# tick-mk-4_7_1.net
KiCad netlist of a schematic drawn in EAGLE
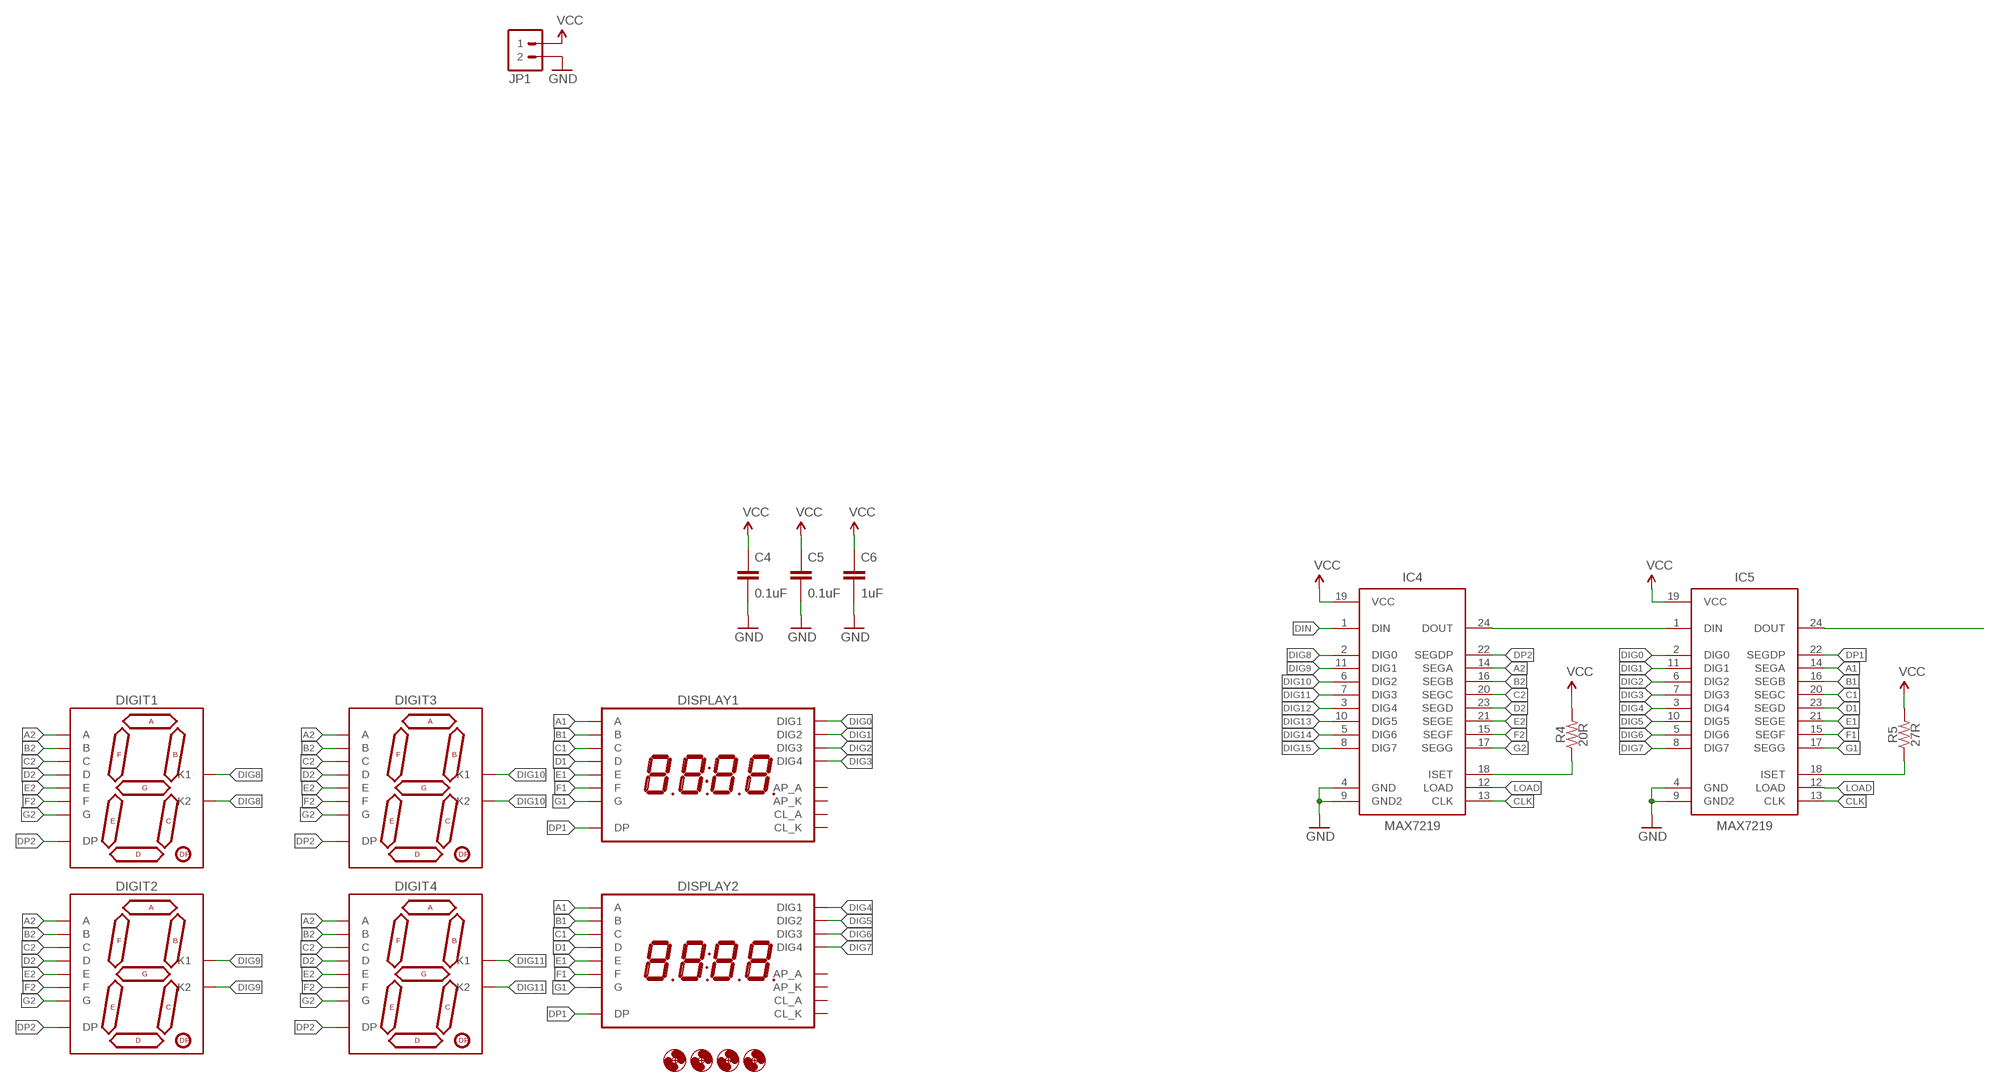
[diagram p0: schematic, sheet 1]

(export (version "E")
  (design (tool "Eeschema 10.0.6"))
  (components
    (comp (ref "C4")
      (value "0.1uF")
      (footprint "eagle-import:C025-024X044")
      (libsource (lib "eagle-import") (part "CAPACITOR-CERAMIC025-024X044"))
    )
    (comp (ref "C5")
      (value "0.1uF")
      (footprint "eagle-import:C025-024X044")
      (libsource (lib "eagle-import") (part "CAPACITOR-CERAMIC025-024X044"))
    )
    (comp (ref "C6")
      (value "1uF")
      (footprint "eagle-import:C025-024X044")
      (libsource (lib "eagle-import") (part "CAPACITOR-CERAMIC025-024X044"))
    )
    (comp (ref "DIGIT1")
      (value "7SEG_1DIGPTH-25.4MM-BARE")
      (footprint "eagle-import:7SEG_1DIG_25.4MM_NOSILK")
      (libsource (lib "eagle-import") (part "7SEG_1DIGPTH-25.4MM-BARE"))
    )
    (comp (ref "DIGIT2")
      (value "7SEG_1DIGPTH-25.4MM-BARE")
      (footprint "eagle-import:7SEG_1DIG_25.4MM_NOSILK")
      (libsource (lib "eagle-import") (part "7SEG_1DIGPTH-25.4MM-BARE"))
    )
    (comp (ref "DIGIT3")
      (value "7SEG_1DIGPTH-25.4MM-BARE")
      (footprint "eagle-import:7SEG_1DIG_25.4MM_NOSILK")
      (libsource (lib "eagle-import") (part "7SEG_1DIGPTH-25.4MM-BARE"))
    )
    (comp (ref "DIGIT4")
      (value "7SEG_1DIGPTH-25.4MM-BARE")
      (footprint "eagle-import:7SEG_1DIG_25.4MM_NOSILK")
      (libsource (lib "eagle-import") (part "7SEG_1DIGPTH-25.4MM-BARE"))
    )
    (comp (ref "DISPLAY1")
      (value "7SEG_4DIGIT_COLON_APOS")
      (footprint "eagle-import:7SEG_4DIG_10MM")
      (libsource (lib "eagle-import") (part "7SEG_4DIGIT_COLON_APOS"))
    )
    (comp (ref "DISPLAY2")
      (value "7SEG_4DIGIT_COLON_APOS")
      (footprint "eagle-import:7SEG_4DIG_10MM")
      (libsource (lib "eagle-import") (part "7SEG_4DIGIT_COLON_APOS"))
    )
    (comp (ref "H1")
      (value "HOLE#2")
      (footprint "eagle-import:HOLE-#2")
      (libsource (lib "eagle-import") (part "HOLE#2"))
    )
    (comp (ref "H2")
      (value "HOLE#2")
      (footprint "eagle-import:HOLE-#2")
      (libsource (lib "eagle-import") (part "HOLE#2"))
    )
    (comp (ref "H3")
      (value "HOLE#2")
      (footprint "eagle-import:HOLE-#2")
      (libsource (lib "eagle-import") (part "HOLE#2"))
    )
    (comp (ref "H4")
      (value "HOLE#2")
      (footprint "eagle-import:HOLE-#2")
      (libsource (lib "eagle-import") (part "HOLE#2"))
    )
    (comp (ref "IC4")
      (value "MAX7219")
      (footprint "eagle-import:SO24W")
      (libsource (lib "eagle-import") (part "MAX7219SOIC-W"))
    )
    (comp (ref "IC5")
      (value "MAX7219")
      (footprint "eagle-import:SO24W")
      (libsource (lib "eagle-import") (part "MAX7219SOIC-W"))
    )
    (comp (ref "JP1")
      (value "M02JST-XH-VERT")
      (footprint "eagle-import:JST-2-XH-VERT-PTH")
      (libsource (lib "eagle-import") (part "M02JST-XH-VERT"))
    )
    (comp (ref "R4")
      (value "20R")
      (footprint "eagle-import:RESISTOR-AXIAL-PTH-7.62MM")
      (libsource (lib "eagle-import") (part "RESISTORPTH-AXIAL-7.62MM"))
    )
    (comp (ref "R5")
      (value "27R")
      (footprint "eagle-import:RESISTOR-AXIAL-PTH-7.62MM")
      (libsource (lib "eagle-import") (part "RESISTORPTH-AXIAL-7.62MM"))
    )
  )
  (nets
    (net (code "1") (name "A1") (class "Default")
      (node (ref "DISPLAY1") (pin "14") (pinfunction "A_14") (pintype "passive"))
      (node (ref "DISPLAY2") (pin "14") (pinfunction "A_14") (pintype "passive"))
      (node (ref "IC5") (pin "14") (pinfunction "SEGA_14") (pintype "bidirectional"))
    )
    (net (code "2") (name "A2") (class "Default")
      (node (ref "DIGIT1") (pin "7") (pinfunction "A_7") (pintype "bidirectional"))
      (node (ref "DIGIT2") (pin "7") (pinfunction "A_7") (pintype "bidirectional"))
      (node (ref "DIGIT3") (pin "7") (pinfunction "A_7") (pintype "bidirectional"))
      (node (ref "DIGIT4") (pin "7") (pinfunction "A_7") (pintype "bidirectional"))
      (node (ref "IC4") (pin "14") (pinfunction "SEGA_14") (pintype "bidirectional"))
    )
    (net (code "3") (name "B1") (class "Default")
      (node (ref "DISPLAY1") (pin "16") (pinfunction "B_16") (pintype "passive"))
      (node (ref "DISPLAY2") (pin "16") (pinfunction "B_16") (pintype "passive"))
      (node (ref "IC5") (pin "16") (pinfunction "SEGB_16") (pintype "bidirectional"))
    )
    (net (code "4") (name "B2") (class "Default")
      (node (ref "DIGIT1") (pin "6") (pinfunction "B_6") (pintype "bidirectional"))
      (node (ref "DIGIT2") (pin "6") (pinfunction "B_6") (pintype "bidirectional"))
      (node (ref "DIGIT3") (pin "6") (pinfunction "B_6") (pintype "bidirectional"))
      (node (ref "DIGIT4") (pin "6") (pinfunction "B_6") (pintype "bidirectional"))
      (node (ref "IC4") (pin "16") (pinfunction "SEGB_16") (pintype "bidirectional"))
    )
    (net (code "5") (name "C1") (class "Default")
      (node (ref "DISPLAY1") (pin "13") (pinfunction "C_13") (pintype "passive"))
      (node (ref "DISPLAY2") (pin "13") (pinfunction "C_13") (pintype "passive"))
      (node (ref "IC5") (pin "20") (pinfunction "SEGC_20") (pintype "bidirectional"))
    )
    (net (code "6") (name "C2") (class "Default")
      (node (ref "DIGIT1") (pin "4") (pinfunction "C_4") (pintype "bidirectional"))
      (node (ref "DIGIT2") (pin "4") (pinfunction "C_4") (pintype "bidirectional"))
      (node (ref "DIGIT3") (pin "4") (pinfunction "C_4") (pintype "bidirectional"))
      (node (ref "DIGIT4") (pin "4") (pinfunction "C_4") (pintype "bidirectional"))
      (node (ref "IC4") (pin "20") (pinfunction "SEGC_20") (pintype "bidirectional"))
    )
    (net (code "7") (name "CLK") (class "Default")
      (node (ref "IC4") (pin "13") (pinfunction "CLK_13") (pintype "bidirectional"))
      (node (ref "IC5") (pin "13") (pinfunction "CLK_13") (pintype "bidirectional"))
    )
    (net (code "8") (name "D1") (class "Default")
      (node (ref "DISPLAY1") (pin "3") (pinfunction "D_3") (pintype "passive"))
      (node (ref "DISPLAY2") (pin "3") (pinfunction "D_3") (pintype "passive"))
      (node (ref "IC5") (pin "23") (pinfunction "SEGD_23") (pintype "bidirectional"))
    )
    (net (code "9") (name "D2") (class "Default")
      (node (ref "DIGIT1") (pin "2") (pinfunction "D_2") (pintype "bidirectional"))
      (node (ref "DIGIT2") (pin "2") (pinfunction "D_2") (pintype "bidirectional"))
      (node (ref "DIGIT3") (pin "2") (pinfunction "D_2") (pintype "bidirectional"))
      (node (ref "DIGIT4") (pin "2") (pinfunction "D_2") (pintype "bidirectional"))
      (node (ref "IC4") (pin "23") (pinfunction "SEGD_23") (pintype "bidirectional"))
    )
    (net (code "10") (name "DIG0") (class "Default")
      (node (ref "DISPLAY1") (pin "1") (pinfunction "DIG1_1") (pintype "passive"))
      (node (ref "IC5") (pin "2") (pinfunction "DIG0_2") (pintype "bidirectional"))
    )
    (net (code "11") (name "DIG1") (class "Default")
      (node (ref "DISPLAY1") (pin "2") (pinfunction "DIG2_2") (pintype "passive"))
      (node (ref "IC5") (pin "11") (pinfunction "DIG1_11") (pintype "bidirectional"))
    )
    (net (code "12") (name "DIG2") (class "Default")
      (node (ref "DISPLAY1") (pin "6") (pinfunction "DIG3_6") (pintype "passive"))
      (node (ref "IC5") (pin "6") (pinfunction "DIG2_6") (pintype "bidirectional"))
    )
    (net (code "13") (name "DIG3") (class "Default")
      (node (ref "DISPLAY1") (pin "8") (pinfunction "DIG4_8") (pintype "passive"))
      (node (ref "IC5") (pin "7") (pinfunction "DIG3_7") (pintype "bidirectional"))
    )
    (net (code "14") (name "DIG4") (class "Default")
      (node (ref "DISPLAY2") (pin "1") (pinfunction "DIG1_1") (pintype "passive"))
      (node (ref "IC5") (pin "3") (pinfunction "DIG4_3") (pintype "bidirectional"))
    )
    (net (code "15") (name "DIG5") (class "Default")
      (node (ref "DISPLAY2") (pin "2") (pinfunction "DIG2_2") (pintype "passive"))
      (node (ref "IC5") (pin "10") (pinfunction "DIG5_10") (pintype "bidirectional"))
    )
    (net (code "16") (name "DIG6") (class "Default")
      (node (ref "DISPLAY2") (pin "6") (pinfunction "DIG3_6") (pintype "passive"))
      (node (ref "IC5") (pin "5") (pinfunction "DIG6_5") (pintype "bidirectional"))
    )
    (net (code "17") (name "DIG7") (class "Default")
      (node (ref "DISPLAY2") (pin "8") (pinfunction "DIG4_8") (pintype "passive"))
      (node (ref "IC5") (pin "8") (pinfunction "DIG7_8") (pintype "bidirectional"))
    )
    (net (code "18") (name "DIG8") (class "Default")
      (node (ref "DIGIT1") (pin "3") (pinfunction "K1_3") (pintype "bidirectional"))
      (node (ref "DIGIT1") (pin "8") (pinfunction "K2_8") (pintype "bidirectional"))
      (node (ref "IC4") (pin "2") (pinfunction "DIG0_2") (pintype "bidirectional"))
    )
    (net (code "19") (name "DIG9") (class "Default")
      (node (ref "DIGIT2") (pin "3") (pinfunction "K1_3") (pintype "bidirectional"))
      (node (ref "DIGIT2") (pin "8") (pinfunction "K2_8") (pintype "bidirectional"))
      (node (ref "IC4") (pin "11") (pinfunction "DIG1_11") (pintype "bidirectional"))
    )
    (net (code "20") (name "DIG10") (class "Default")
      (node (ref "DIGIT3") (pin "3") (pinfunction "K1_3") (pintype "bidirectional"))
      (node (ref "DIGIT3") (pin "8") (pinfunction "K2_8") (pintype "bidirectional"))
      (node (ref "IC4") (pin "6") (pinfunction "DIG2_6") (pintype "bidirectional"))
    )
    (net (code "21") (name "DIG11") (class "Default")
      (node (ref "DIGIT4") (pin "3") (pinfunction "K1_3") (pintype "bidirectional"))
      (node (ref "DIGIT4") (pin "8") (pinfunction "K2_8") (pintype "bidirectional"))
      (node (ref "IC4") (pin "7") (pinfunction "DIG3_7") (pintype "bidirectional"))
    )
    (net (code "22") (name "DIG12") (class "Default")
      (node (ref "IC4") (pin "3") (pinfunction "DIG4_3") (pintype "bidirectional"))
    )
    (net (code "23") (name "DIG13") (class "Default")
      (node (ref "IC4") (pin "10") (pinfunction "DIG5_10") (pintype "bidirectional"))
    )
    (net (code "24") (name "DIG14") (class "Default")
      (node (ref "IC4") (pin "5") (pinfunction "DIG6_5") (pintype "bidirectional"))
    )
    (net (code "25") (name "DIG15") (class "Default")
      (node (ref "IC4") (pin "8") (pinfunction "DIG7_8") (pintype "bidirectional"))
    )
    (net (code "26") (name "DIN") (class "Default")
      (node (ref "IC4") (pin "1") (pinfunction "DIN_1") (pintype "bidirectional"))
    )
    (net (code "27") (name "DP1") (class "Default")
      (node (ref "DISPLAY1") (pin "7") (pinfunction "DP_7") (pintype "passive"))
      (node (ref "DISPLAY2") (pin "7") (pinfunction "DP_7") (pintype "passive"))
      (node (ref "IC5") (pin "22") (pinfunction "SEGDP_22") (pintype "bidirectional"))
    )
    (net (code "28") (name "DP2") (class "Default")
      (node (ref "DIGIT1") (pin "5") (pinfunction "DP_5") (pintype "bidirectional"))
      (node (ref "DIGIT2") (pin "5") (pinfunction "DP_5") (pintype "bidirectional"))
      (node (ref "DIGIT3") (pin "5") (pinfunction "DP_5") (pintype "bidirectional"))
      (node (ref "DIGIT4") (pin "5") (pinfunction "DP_5") (pintype "bidirectional"))
      (node (ref "IC4") (pin "22") (pinfunction "SEGDP_22") (pintype "bidirectional"))
    )
    (net (code "29") (name "E1") (class "Default")
      (node (ref "DISPLAY1") (pin "5") (pinfunction "E_5") (pintype "passive"))
      (node (ref "DISPLAY2") (pin "5") (pinfunction "E_5") (pintype "passive"))
      (node (ref "IC5") (pin "21") (pinfunction "SEGE_21") (pintype "bidirectional"))
    )
    (net (code "30") (name "E2") (class "Default")
      (node (ref "DIGIT1") (pin "1") (pinfunction "E_1") (pintype "bidirectional"))
      (node (ref "DIGIT2") (pin "1") (pinfunction "E_1") (pintype "bidirectional"))
      (node (ref "DIGIT3") (pin "1") (pinfunction "E_1") (pintype "bidirectional"))
      (node (ref "DIGIT4") (pin "1") (pinfunction "E_1") (pintype "bidirectional"))
      (node (ref "IC4") (pin "21") (pinfunction "SEGE_21") (pintype "bidirectional"))
    )
    (net (code "31") (name "F1") (class "Default")
      (node (ref "DISPLAY1") (pin "11") (pinfunction "F_11") (pintype "passive"))
      (node (ref "DISPLAY2") (pin "11") (pinfunction "F_11") (pintype "passive"))
      (node (ref "IC5") (pin "15") (pinfunction "SEGF_15") (pintype "bidirectional"))
    )
    (net (code "32") (name "F2") (class "Default")
      (node (ref "DIGIT1") (pin "9") (pinfunction "F_9") (pintype "bidirectional"))
      (node (ref "DIGIT2") (pin "9") (pinfunction "F_9") (pintype "bidirectional"))
      (node (ref "DIGIT3") (pin "9") (pinfunction "F_9") (pintype "bidirectional"))
      (node (ref "DIGIT4") (pin "9") (pinfunction "F_9") (pintype "bidirectional"))
      (node (ref "IC4") (pin "15") (pinfunction "SEGF_15") (pintype "bidirectional"))
    )
    (net (code "33") (name "G1") (class "Default")
      (node (ref "DISPLAY1") (pin "15") (pinfunction "G_15") (pintype "passive"))
      (node (ref "DISPLAY2") (pin "15") (pinfunction "G_15") (pintype "passive"))
      (node (ref "IC5") (pin "17") (pinfunction "SEGG_17") (pintype "bidirectional"))
    )
    (net (code "34") (name "G2") (class "Default")
      (node (ref "DIGIT1") (pin "10") (pinfunction "G_10") (pintype "bidirectional"))
      (node (ref "DIGIT2") (pin "10") (pinfunction "G_10") (pintype "bidirectional"))
      (node (ref "DIGIT3") (pin "10") (pinfunction "G_10") (pintype "bidirectional"))
      (node (ref "DIGIT4") (pin "10") (pinfunction "G_10") (pintype "bidirectional"))
      (node (ref "IC4") (pin "17") (pinfunction "SEGG_17") (pintype "bidirectional"))
    )
    (net (code "35") (name "GND") (class "Default")
      (node (ref "C4") (pin "2") (pinfunction "2_2") (pintype "passive"))
      (node (ref "C5") (pin "2") (pinfunction "2_2") (pintype "passive"))
      (node (ref "C6") (pin "2") (pinfunction "2_2") (pintype "passive"))
      (node (ref "IC4") (pin "4") (pinfunction "GND_4") (pintype "bidirectional"))
      (node (ref "IC4") (pin "9") (pinfunction "GND2_9") (pintype "bidirectional"))
      (node (ref "IC5") (pin "4") (pinfunction "GND_4") (pintype "bidirectional"))
      (node (ref "IC5") (pin "9") (pinfunction "GND2_9") (pintype "bidirectional"))
      (node (ref "JP1") (pin "2") (pinfunction "2_2") (pintype "passive"))
    )
    (net (code "36") (name "LOAD") (class "Default")
      (node (ref "IC4") (pin "12") (pinfunction "LOAD_12") (pintype "bidirectional"))
      (node (ref "IC5") (pin "12") (pinfunction "LOAD_12") (pintype "bidirectional"))
    )
    (net (code "37") (name "Net-(IC4-DOUT)") (class "Default")
      (node (ref "IC4") (pin "24") (pinfunction "DOUT_24") (pintype "bidirectional"))
      (node (ref "IC5") (pin "1") (pinfunction "DIN_1") (pintype "bidirectional"))
    )
    (net (code "38") (name "Net-(IC4-ISET)") (class "Default")
      (node (ref "IC4") (pin "18") (pinfunction "ISET_18") (pintype "bidirectional"))
      (node (ref "R4") (pin "P$1") (pinfunction "1_P$1") (pintype "passive"))
    )
    (net (code "39") (name "Net-(IC5-ISET)") (class "Default")
      (node (ref "IC5") (pin "18") (pinfunction "ISET_18") (pintype "bidirectional"))
      (node (ref "R5") (pin "P$1") (pinfunction "1_P$1") (pintype "passive"))
    )
    (net (code "40") (name "VCC") (class "Default")
      (node (ref "C4") (pin "1") (pinfunction "1_1") (pintype "passive"))
      (node (ref "C5") (pin "1") (pinfunction "1_1") (pintype "passive"))
      (node (ref "C6") (pin "1") (pinfunction "1_1") (pintype "passive"))
      (node (ref "IC4") (pin "19") (pinfunction "VCC_19") (pintype "bidirectional"))
      (node (ref "IC5") (pin "19") (pinfunction "VCC_19") (pintype "bidirectional"))
      (node (ref "JP1") (pin "1") (pinfunction "1_1") (pintype "passive"))
      (node (ref "R4") (pin "P$2") (pinfunction "2_P$2") (pintype "passive"))
      (node (ref "R5") (pin "P$2") (pinfunction "2_P$2") (pintype "passive"))
    )
    (net (code "41") (name "unconnected-(DISPLAY1-AP_A-Pad10)") (class "Default")
      (node (ref "DISPLAY1") (pin "10") (pinfunction "AP_A_10") (pintype "bidirectional"))
    )
    (net (code "42") (name "unconnected-(DISPLAY1-AP_K-Pad9)") (class "Default")
      (node (ref "DISPLAY1") (pin "9") (pinfunction "AP_K_9") (pintype "bidirectional"))
    )
    (net (code "43") (name "unconnected-(DISPLAY1-CL_A-Pad4)") (class "Default")
      (node (ref "DISPLAY1") (pin "4") (pinfunction "CL_A_4") (pintype "passive"))
    )
    (net (code "44") (name "unconnected-(DISPLAY1-CL_K-Pad12)") (class "Default")
      (node (ref "DISPLAY1") (pin "12") (pinfunction "CL_K_12") (pintype "passive"))
    )
    (net (code "45") (name "unconnected-(DISPLAY2-AP_A-Pad10)") (class "Default")
      (node (ref "DISPLAY2") (pin "10") (pinfunction "AP_A_10") (pintype "bidirectional"))
    )
    (net (code "46") (name "unconnected-(DISPLAY2-AP_K-Pad9)") (class "Default")
      (node (ref "DISPLAY2") (pin "9") (pinfunction "AP_K_9") (pintype "bidirectional"))
    )
    (net (code "47") (name "unconnected-(DISPLAY2-CL_A-Pad4)") (class "Default")
      (node (ref "DISPLAY2") (pin "4") (pinfunction "CL_A_4") (pintype "passive"))
    )
    (net (code "48") (name "unconnected-(DISPLAY2-CL_K-Pad12)") (class "Default")
      (node (ref "DISPLAY2") (pin "12") (pinfunction "CL_K_12") (pintype "passive"))
    )
    (net (code "49") (name "unconnected-(IC5-DOUT-Pad24)") (class "Default")
      (node (ref "IC5") (pin "24") (pinfunction "DOUT_24") (pintype "bidirectional"))
    )
  )
)
